# MI0283QT_v12b.net
KiCad netlist of a schematic drawn in EAGLE
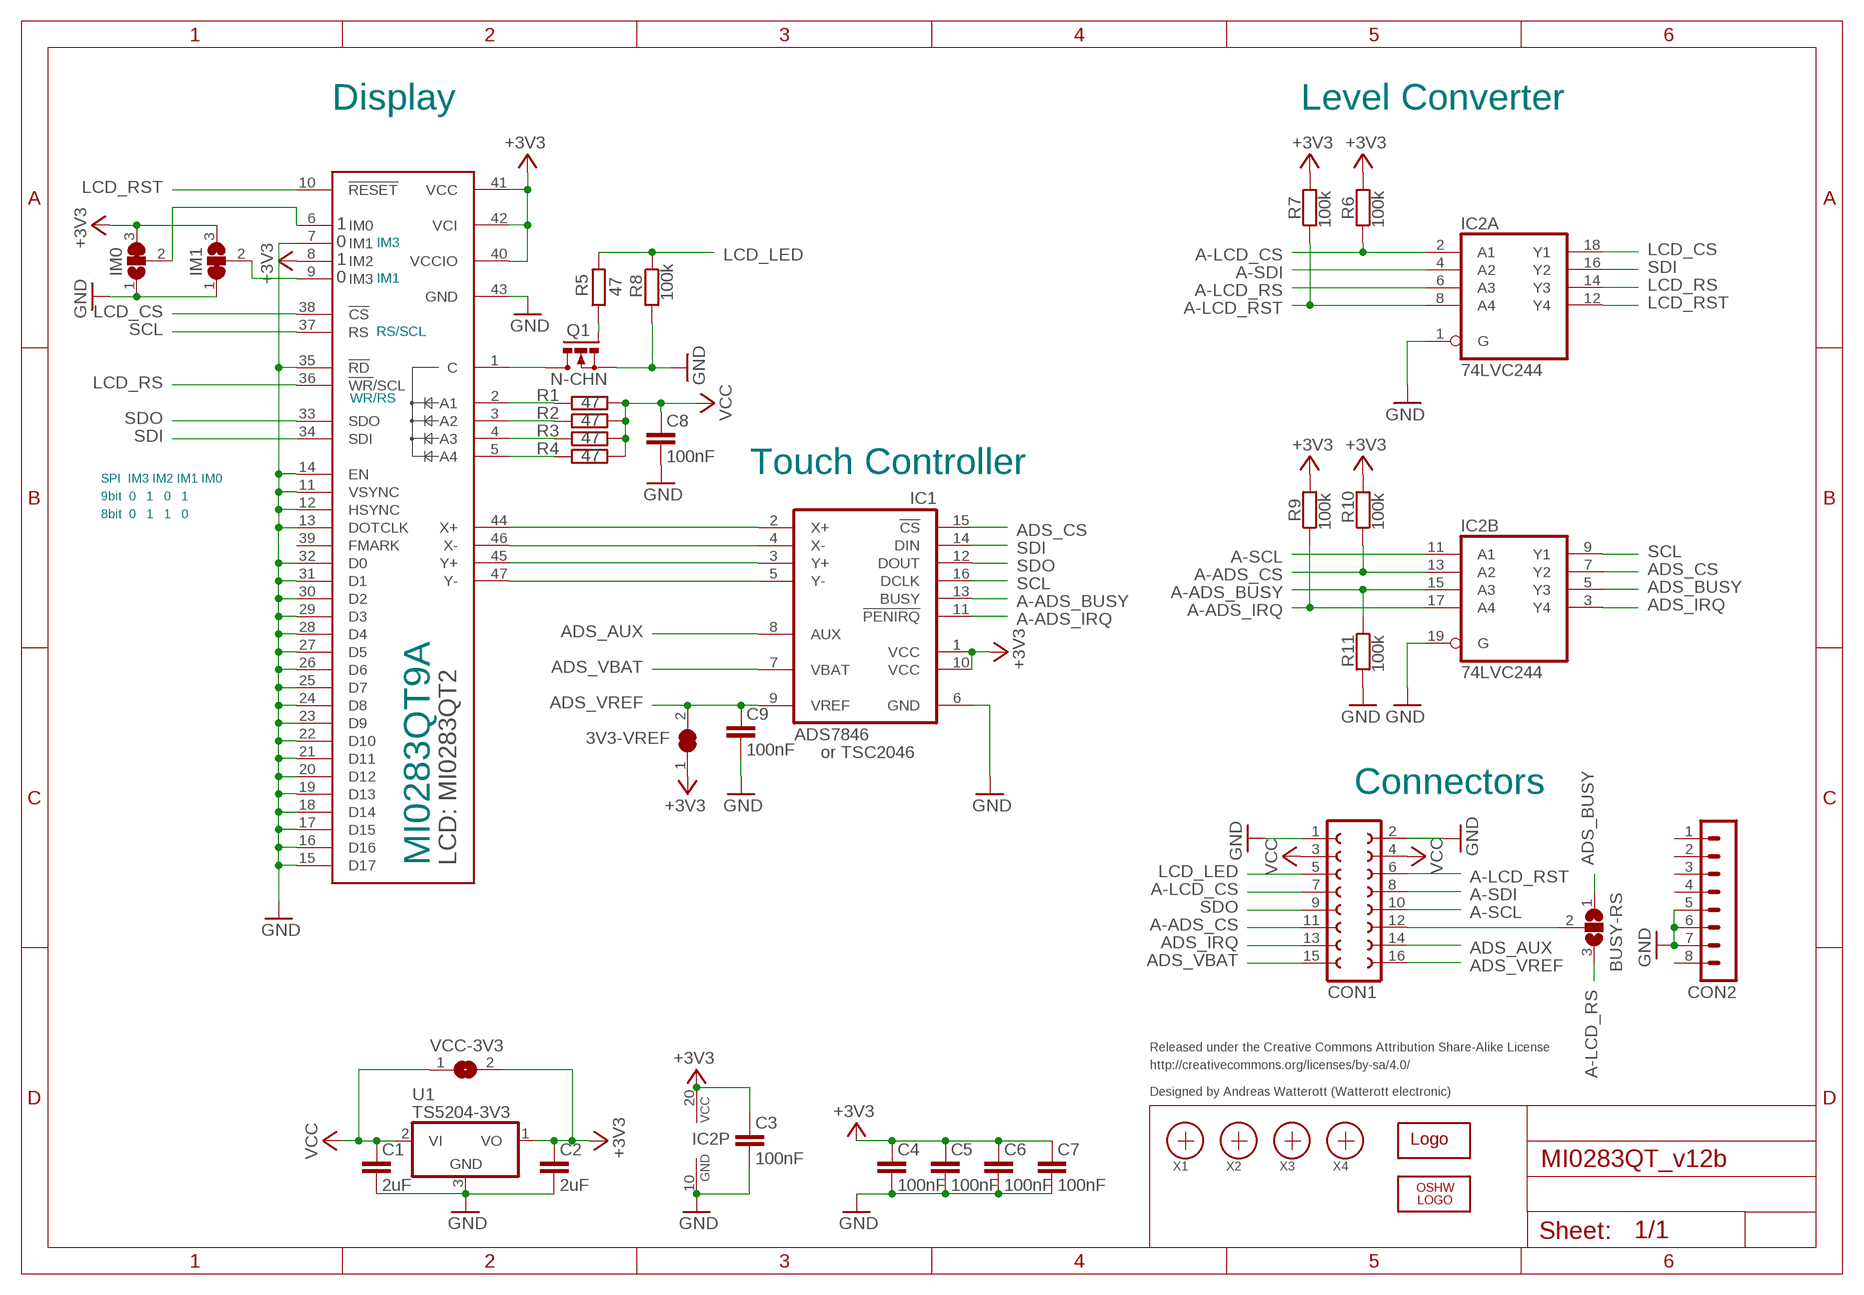
[diagram p0: schematic, sheet 1]

(export (version "E")
  (design (tool "Eeschema 10.0.6"))
  (components
    (comp (ref "3V3-VREF")
      (value "SJ")
      (footprint "eagle-import:SJ")
      (libsource (lib "eagle-import") (part "SJ"))
    )
    (comp (ref "BUSY-RS")
      (value "SJ2W")
      (footprint "eagle-import:SJ_2")
      (libsource (lib "eagle-import") (part "SJ2W"))
    )
    (comp (ref "C1")
      (value "2uF")
      (footprint "eagle-import:C0805")
      (libsource (lib "eagle-import") (part "C-EUC0805"))
    )
    (comp (ref "C2")
      (value "2uF")
      (footprint "eagle-import:C0805")
      (libsource (lib "eagle-import") (part "C-EUC0805"))
    )
    (comp (ref "C3")
      (value "100nF")
      (footprint "eagle-import:C0603")
      (libsource (lib "eagle-import") (part "C-EUC0603"))
    )
    (comp (ref "C4")
      (value "100nF")
      (footprint "eagle-import:C0603")
      (libsource (lib "eagle-import") (part "C-EUC0603"))
    )
    (comp (ref "C5")
      (value "100nF")
      (footprint "eagle-import:C0603")
      (libsource (lib "eagle-import") (part "C-EUC0603"))
    )
    (comp (ref "C6")
      (value "100nF")
      (footprint "eagle-import:C0603")
      (libsource (lib "eagle-import") (part "C-EUC0603"))
    )
    (comp (ref "C7")
      (value "100nF")
      (footprint "eagle-import:C0603")
      (libsource (lib "eagle-import") (part "C-EUC0603"))
    )
    (comp (ref "C8")
      (value "100nF")
      (footprint "eagle-import:C0603")
      (libsource (lib "eagle-import") (part "C-EUC0603"))
    )
    (comp (ref "C9")
      (value "100nF")
      (footprint "eagle-import:C0603")
      (libsource (lib "eagle-import") (part "C-EUC0603"))
    )
    (comp (ref "CON1")
      (value "FE08-2")
      (footprint "eagle-import:FE08-2")
      (libsource (lib "eagle-import") (part "FE08-2"))
    )
    (comp (ref "CON2")
      (value "MA08-1")
      (footprint "eagle-import:MA08-1")
      (libsource (lib "eagle-import") (part "MA08-1"))
    )
    (comp (ref "IC1")
      (value "ADS7846")
      (footprint "eagle-import:SSOP16")
      (libsource (lib "eagle-import") (part "ADS7846"))
    )
    (comp (ref "IC2")
      (value "74LVC244")
      (footprint "eagle-import:SO20W")
      (libsource (lib "eagle-import") (part "74244DWHC"))
    )
    (comp (ref "IM0")
      (value "SJ2W")
      (footprint "eagle-import:SJ_2")
      (libsource (lib "eagle-import") (part "SJ2W"))
    )
    (comp (ref "IM1")
      (value "SJ2W")
      (footprint "eagle-import:SJ_2")
      (libsource (lib "eagle-import") (part "SJ2W"))
    )
    (comp (ref "LCD")
      (value "MI0283QT")
      (footprint "eagle-import:MI0283QT")
      (libsource (lib "eagle-import") (part "MI0283QT"))
    )
    (comp (ref "LOGO1")
      (value "OSHW_LOGO_6MILX0150-NT")
      (footprint "eagle-import:OSHW_6X150_NOTEXT")
      (libsource (lib "eagle-import") (part "OSHW_LOGO_6MILX0150-NT"))
    )
    (comp (ref "Q1")
      (value "N-CHN")
      (footprint "eagle-import:MICRO3")
      (libsource (lib "eagle-import") (part "IRLML2502"))
    )
    (comp (ref "R1")
      (value "47")
      (footprint "eagle-import:R0603")
      (libsource (lib "eagle-import") (part "R-EU_R0603"))
    )
    (comp (ref "R2")
      (value "47")
      (footprint "eagle-import:R0603")
      (libsource (lib "eagle-import") (part "R-EU_R0603"))
    )
    (comp (ref "R3")
      (value "47")
      (footprint "eagle-import:R0603")
      (libsource (lib "eagle-import") (part "R-EU_R0603"))
    )
    (comp (ref "R4")
      (value "47")
      (footprint "eagle-import:R0603")
      (libsource (lib "eagle-import") (part "R-EU_R0603"))
    )
    (comp (ref "R5")
      (value "47")
      (footprint "eagle-import:R0603")
      (libsource (lib "eagle-import") (part "R-EU_R0603"))
    )
    (comp (ref "R6")
      (value "100k")
      (footprint "eagle-import:R0603")
      (libsource (lib "eagle-import") (part "R-EU_R0603"))
    )
    (comp (ref "R7")
      (value "100k")
      (footprint "eagle-import:R0603")
      (libsource (lib "eagle-import") (part "R-EU_R0603"))
    )
    (comp (ref "R8")
      (value "100k")
      (footprint "eagle-import:R0603")
      (libsource (lib "eagle-import") (part "R-EU_R0603"))
    )
    (comp (ref "R9")
      (value "100k")
      (footprint "eagle-import:R0603")
      (libsource (lib "eagle-import") (part "R-EU_R0603"))
    )
    (comp (ref "R10")
      (value "100k")
      (footprint "eagle-import:R0603")
      (libsource (lib "eagle-import") (part "R-EU_R0603"))
    )
    (comp (ref "R11")
      (value "100k")
      (footprint "eagle-import:R0603")
      (libsource (lib "eagle-import") (part "R-EU_R0603"))
    )
    (comp (ref "U$1")
      (value "WE-LOGO")
      (footprint "eagle-import:WE-LOGO")
      (libsource (lib "eagle-import") (part "WE-LOGO"))
    )
    (comp (ref "U1")
      (value "TS5204-3V3")
      (footprint "eagle-import:SOT23")
      (libsource (lib "eagle-import") (part "TS5204"))
    )
    (comp (ref "VCC-3V3")
      (value "SJ")
      (footprint "eagle-import:SJ")
      (libsource (lib "eagle-import") (part "SJ"))
    )
    (comp (ref "X1")
      (value "PASSER")
      (footprint "eagle-import:PASSER")
      (libsource (lib "eagle-import") (part "PASSER"))
    )
    (comp (ref "X2")
      (value "PASSER")
      (footprint "eagle-import:PASSER")
      (libsource (lib "eagle-import") (part "PASSER"))
    )
    (comp (ref "X3")
      (value "PASSER")
      (footprint "eagle-import:PASSER")
      (libsource (lib "eagle-import") (part "PASSER"))
    )
    (comp (ref "X4")
      (value "PASSER")
      (footprint "eagle-import:PASSER")
      (libsource (lib "eagle-import") (part "PASSER"))
    )
  )
  (nets
    (net (code "1") (name "+3V3") (class "Default")
      (node (ref "3V3-VREF") (pin "1") (pinfunction "1_1") (pintype "passive"))
      (node (ref "C2") (pin "1") (pinfunction "1_1") (pintype "passive"))
      (node (ref "C3") (pin "1") (pinfunction "1_1") (pintype "passive"))
      (node (ref "C4") (pin "1") (pinfunction "1_1") (pintype "passive"))
      (node (ref "C5") (pin "1") (pinfunction "1_1") (pintype "passive"))
      (node (ref "C6") (pin "1") (pinfunction "1_1") (pintype "passive"))
      (node (ref "C7") (pin "1") (pinfunction "1_1") (pintype "passive"))
      (node (ref "IC1") (pin "1") (pinfunction "VCC_1") (pintype "power_in"))
      (node (ref "IC1") (pin "10") (pinfunction "VCC_10") (pintype "power_in"))
      (node (ref "IC2") (pin "20") (pinfunction "VCC_20") (pintype "power_in"))
      (node (ref "IM0") (pin "3") (pinfunction "3_3") (pintype "passive"))
      (node (ref "IM1") (pin "3") (pinfunction "3_3") (pintype "passive"))
      (node (ref "LCD") (pin "40") (pinfunction "VCCIO_40") (pintype "power_in"))
      (node (ref "LCD") (pin "41") (pinfunction "VCC_41") (pintype "power_in"))
      (node (ref "LCD") (pin "42") (pinfunction "VCI_42") (pintype "power_in"))
      (node (ref "LCD") (pin "8") (pinfunction "IM2_8") (pintype "input"))
      (node (ref "R10") (pin "2") (pinfunction "2_2") (pintype "passive"))
      (node (ref "R6") (pin "2") (pinfunction "2_2") (pintype "passive"))
      (node (ref "R7") (pin "2") (pinfunction "2_2") (pintype "passive"))
      (node (ref "R9") (pin "2") (pinfunction "2_2") (pintype "passive"))
      (node (ref "U1") (pin "1") (pinfunction "VO_1") (pintype "passive"))
      (node (ref "VCC-3V3") (pin "2") (pinfunction "2_2") (pintype "passive"))
    )
    (net (code "2") (name "/A-ADS_BUSY") (class "Default")
      (node (ref "IC1") (pin "13") (pinfunction "BUSY_13") (pintype "output"))
      (node (ref "IC2") (pin "15") (pinfunction "A3_15") (pintype "input"))
      (node (ref "R11") (pin "1") (pinfunction "1_1") (pintype "passive"))
    )
    (net (code "3") (name "/A-ADS_CS") (class "Default")
      (node (ref "CON1") (pin "11") (pinfunction "11_11") (pintype "passive"))
      (node (ref "IC2") (pin "13") (pinfunction "A2_13") (pintype "input"))
      (node (ref "R10") (pin "1") (pinfunction "1_1") (pintype "passive"))
    )
    (net (code "4") (name "/A-ADS_IRQ") (class "Default")
      (node (ref "IC1") (pin "11") (pinfunction "~{PENIRQ}_11") (pintype "output"))
      (node (ref "IC2") (pin "17") (pinfunction "A4_17") (pintype "input"))
      (node (ref "R9") (pin "1") (pinfunction "1_1") (pintype "passive"))
    )
    (net (code "5") (name "/A-LCD_CS") (class "Default")
      (node (ref "CON1") (pin "7") (pinfunction "7_7") (pintype "passive"))
      (node (ref "IC2") (pin "2") (pinfunction "A1_2") (pintype "input"))
      (node (ref "R6") (pin "1") (pinfunction "1_1") (pintype "passive"))
    )
    (net (code "6") (name "/A-LCD_RS") (class "Default")
      (node (ref "BUSY-RS") (pin "3") (pinfunction "3_3") (pintype "passive"))
      (node (ref "IC2") (pin "6") (pinfunction "A3_6") (pintype "input"))
    )
    (net (code "7") (name "/A-LCD_RST") (class "Default")
      (node (ref "CON1") (pin "6") (pinfunction "6_6") (pintype "passive"))
      (node (ref "IC2") (pin "8") (pinfunction "A4_8") (pintype "input"))
      (node (ref "R7") (pin "1") (pinfunction "1_1") (pintype "passive"))
    )
    (net (code "8") (name "/A-SCL") (class "Default")
      (node (ref "CON1") (pin "10") (pinfunction "10_10") (pintype "passive"))
      (node (ref "IC2") (pin "11") (pinfunction "A1_11") (pintype "input"))
    )
    (net (code "9") (name "/A-SDI") (class "Default")
      (node (ref "CON1") (pin "8") (pinfunction "8_8") (pintype "passive"))
      (node (ref "IC2") (pin "4") (pinfunction "A2_4") (pintype "input"))
    )
    (net (code "10") (name "/ADS_AUX") (class "Default")
      (node (ref "CON1") (pin "14") (pinfunction "14_14") (pintype "passive"))
      (node (ref "IC1") (pin "8") (pinfunction "AUX_8") (pintype "input"))
    )
    (net (code "11") (name "/ADS_BUSY") (class "Default")
      (node (ref "BUSY-RS") (pin "1") (pinfunction "1_1") (pintype "passive"))
      (node (ref "IC2") (pin "5") (pinfunction "Y3_5") (pintype "tri_state"))
    )
    (net (code "12") (name "/ADS_CS") (class "Default")
      (node (ref "IC1") (pin "15") (pinfunction "~{CS}_15") (pintype "input"))
      (node (ref "IC2") (pin "7") (pinfunction "Y2_7") (pintype "tri_state"))
    )
    (net (code "13") (name "/ADS_IRQ") (class "Default")
      (node (ref "CON1") (pin "13") (pinfunction "13_13") (pintype "passive"))
      (node (ref "IC2") (pin "3") (pinfunction "Y4_3") (pintype "tri_state"))
    )
    (net (code "14") (name "/ADS_VBAT") (class "Default")
      (node (ref "CON1") (pin "15") (pinfunction "15_15") (pintype "passive"))
      (node (ref "IC1") (pin "7") (pinfunction "VBAT_7") (pintype "input"))
    )
    (net (code "15") (name "/ADS_VREF") (class "Default")
      (node (ref "3V3-VREF") (pin "2") (pinfunction "2_2") (pintype "passive"))
      (node (ref "C9") (pin "1") (pinfunction "1_1") (pintype "passive"))
      (node (ref "CON1") (pin "16") (pinfunction "16_16") (pintype "passive"))
      (node (ref "IC1") (pin "9") (pinfunction "VREF_9") (pintype "bidirectional"))
    )
    (net (code "16") (name "/LCD_CS") (class "Default")
      (node (ref "IC2") (pin "18") (pinfunction "Y1_18") (pintype "tri_state"))
      (node (ref "LCD") (pin "38") (pinfunction "~{CS}_38") (pintype "input"))
    )
    (net (code "17") (name "/LCD_LED") (class "Default")
      (node (ref "CON1") (pin "5") (pinfunction "5_5") (pintype "passive"))
      (node (ref "R5") (pin "2") (pinfunction "2_2") (pintype "passive"))
      (node (ref "R8") (pin "1") (pinfunction "1_1") (pintype "passive"))
    )
    (net (code "18") (name "/LCD_RS") (class "Default")
      (node (ref "IC2") (pin "14") (pinfunction "Y3_14") (pintype "tri_state"))
      (node (ref "LCD") (pin "36") (pinfunction "~{WR}/SCL_36") (pintype "input"))
    )
    (net (code "19") (name "/LCD_RST") (class "Default")
      (node (ref "IC2") (pin "12") (pinfunction "Y4_12") (pintype "tri_state"))
      (node (ref "LCD") (pin "10") (pinfunction "~{RESET}_10") (pintype "input"))
    )
    (net (code "20") (name "/SCL") (class "Default")
      (node (ref "IC1") (pin "16") (pinfunction "DCLK_16") (pintype "output"))
      (node (ref "IC2") (pin "9") (pinfunction "Y1_9") (pintype "tri_state"))
      (node (ref "LCD") (pin "37") (pinfunction "RS_37") (pintype "input"))
    )
    (net (code "21") (name "/SDI") (class "Default")
      (node (ref "IC1") (pin "14") (pinfunction "DIN_14") (pintype "input"))
      (node (ref "IC2") (pin "16") (pinfunction "Y2_16") (pintype "tri_state"))
      (node (ref "LCD") (pin "34") (pinfunction "SDI_34") (pintype "input"))
    )
    (net (code "22") (name "/SDO") (class "Default")
      (node (ref "CON1") (pin "9") (pinfunction "9_9") (pintype "passive"))
      (node (ref "IC1") (pin "12") (pinfunction "DOUT_12") (pintype "input"))
      (node (ref "LCD") (pin "33") (pinfunction "SDO_33") (pintype "output"))
    )
    (net (code "23") (name "GND") (class "Default")
      (node (ref "C1") (pin "2") (pinfunction "2_2") (pintype "passive"))
      (node (ref "C2") (pin "2") (pinfunction "2_2") (pintype "passive"))
      (node (ref "C3") (pin "2") (pinfunction "2_2") (pintype "passive"))
      (node (ref "C4") (pin "2") (pinfunction "2_2") (pintype "passive"))
      (node (ref "C5") (pin "2") (pinfunction "2_2") (pintype "passive"))
      (node (ref "C6") (pin "2") (pinfunction "2_2") (pintype "passive"))
      (node (ref "C7") (pin "2") (pinfunction "2_2") (pintype "passive"))
      (node (ref "C8") (pin "2") (pinfunction "2_2") (pintype "passive"))
      (node (ref "C9") (pin "2") (pinfunction "2_2") (pintype "passive"))
      (node (ref "CON1") (pin "1") (pinfunction "1_1") (pintype "passive"))
      (node (ref "CON1") (pin "2") (pinfunction "2_2") (pintype "passive"))
      (node (ref "CON2") (pin "5") (pinfunction "5_5") (pintype "passive"))
      (node (ref "CON2") (pin "6") (pinfunction "6_6") (pintype "passive"))
      (node (ref "CON2") (pin "7") (pinfunction "7_7") (pintype "passive"))
      (node (ref "IC1") (pin "6") (pinfunction "GND_6") (pintype "power_in"))
      (node (ref "IC2") (pin "1") (pinfunction "G_1") (pintype "input"))
      (node (ref "IC2") (pin "10") (pinfunction "GND_10") (pintype "power_in"))
      (node (ref "IC2") (pin "19") (pinfunction "G_19") (pintype "input"))
      (node (ref "IM0") (pin "1") (pinfunction "1_1") (pintype "passive"))
      (node (ref "IM1") (pin "1") (pinfunction "1_1") (pintype "passive"))
      (node (ref "LCD") (pin "11") (pinfunction "VSYNC_11") (pintype "input"))
      (node (ref "LCD") (pin "12") (pinfunction "HSYNC_12") (pintype "input"))
      (node (ref "LCD") (pin "13") (pinfunction "DOTCLK_13") (pintype "input"))
      (node (ref "LCD") (pin "14") (pinfunction "EN_14") (pintype "input"))
      (node (ref "LCD") (pin "15") (pinfunction "D17_15") (pintype "input"))
      (node (ref "LCD") (pin "16") (pinfunction "D16_16") (pintype "input"))
      (node (ref "LCD") (pin "17") (pinfunction "D15_17") (pintype "input"))
      (node (ref "LCD") (pin "18") (pinfunction "D14_18") (pintype "input"))
      (node (ref "LCD") (pin "19") (pinfunction "D13_19") (pintype "input"))
      (node (ref "LCD") (pin "20") (pinfunction "D12_20") (pintype "input"))
      (node (ref "LCD") (pin "21") (pinfunction "D11_21") (pintype "input"))
      (node (ref "LCD") (pin "22") (pinfunction "D10_22") (pintype "input"))
      (node (ref "LCD") (pin "23") (pinfunction "D9_23") (pintype "input"))
      (node (ref "LCD") (pin "24") (pinfunction "D8_24") (pintype "input"))
      (node (ref "LCD") (pin "25") (pinfunction "D7_25") (pintype "input"))
      (node (ref "LCD") (pin "26") (pinfunction "D6_26") (pintype "input"))
      (node (ref "LCD") (pin "27") (pinfunction "D5_27") (pintype "input"))
      (node (ref "LCD") (pin "28") (pinfunction "D4_28") (pintype "input"))
      (node (ref "LCD") (pin "29") (pinfunction "D3_29") (pintype "input"))
      (node (ref "LCD") (pin "30") (pinfunction "D2_30") (pintype "input"))
      (node (ref "LCD") (pin "31") (pinfunction "D1_31") (pintype "input"))
      (node (ref "LCD") (pin "32") (pinfunction "D0_32") (pintype "input"))
      (node (ref "LCD") (pin "35") (pinfunction "~{RD}_35") (pintype "input"))
      (node (ref "LCD") (pin "43") (pinfunction "GND_43") (pintype "power_in"))
      (node (ref "LCD") (pin "7") (pinfunction "IM1_7") (pintype "input"))
      (node (ref "Q1") (pin "2") (pinfunction "S_2") (pintype "passive"))
      (node (ref "R11") (pin "2") (pinfunction "2_2") (pintype "passive"))
      (node (ref "R8") (pin "2") (pinfunction "2_2") (pintype "passive"))
      (node (ref "U1") (pin "3") (pinfunction "GND_3") (pintype "passive"))
    )
    (net (code "24") (name "Net-(BUSY-RS-Pad2)") (class "Default")
      (node (ref "BUSY-RS") (pin "2") (pinfunction "2_2") (pintype "passive"))
      (node (ref "CON1") (pin "12") (pinfunction "12_12") (pintype "passive"))
    )
    (net (code "25") (name "Net-(IC1-X+)") (class "Default")
      (node (ref "IC1") (pin "2") (pinfunction "X+_2") (pintype "input"))
      (node (ref "LCD") (pin "44") (pinfunction "X+_44") (pintype "passive"))
    )
    (net (code "26") (name "Net-(IC1-X-)") (class "Default")
      (node (ref "IC1") (pin "4") (pinfunction "X-_4") (pintype "input"))
      (node (ref "LCD") (pin "46") (pinfunction "X-_46") (pintype "passive"))
    )
    (net (code "27") (name "Net-(IC1-Y+)") (class "Default")
      (node (ref "IC1") (pin "3") (pinfunction "Y+_3") (pintype "input"))
      (node (ref "LCD") (pin "45") (pinfunction "Y+_45") (pintype "passive"))
    )
    (net (code "28") (name "Net-(IC1-Y-)") (class "Default")
      (node (ref "IC1") (pin "5") (pinfunction "Y-_5") (pintype "input"))
      (node (ref "LCD") (pin "47") (pinfunction "Y-_47") (pintype "passive"))
    )
    (net (code "29") (name "Net-(LCD-A1)") (class "Default")
      (node (ref "LCD") (pin "2") (pinfunction "A1_2") (pintype "power_in"))
      (node (ref "R1") (pin "1") (pinfunction "1_1") (pintype "passive"))
    )
    (net (code "30") (name "Net-(LCD-A2)") (class "Default")
      (node (ref "LCD") (pin "3") (pinfunction "A2_3") (pintype "power_in"))
      (node (ref "R2") (pin "1") (pinfunction "1_1") (pintype "passive"))
    )
    (net (code "31") (name "Net-(LCD-A3)") (class "Default")
      (node (ref "LCD") (pin "4") (pinfunction "A3_4") (pintype "power_in"))
      (node (ref "R3") (pin "1") (pinfunction "1_1") (pintype "passive"))
    )
    (net (code "32") (name "Net-(LCD-A4)") (class "Default")
      (node (ref "LCD") (pin "5") (pinfunction "A4_5") (pintype "power_in"))
      (node (ref "R4") (pin "1") (pinfunction "1_1") (pintype "passive"))
    )
    (net (code "33") (name "Net-(LCD-C)") (class "Default")
      (node (ref "LCD") (pin "1") (pinfunction "C_1") (pintype "power_in"))
      (node (ref "Q1") (pin "3") (pinfunction "D_3") (pintype "passive"))
    )
    (net (code "34") (name "Net-(LCD-IM0)") (class "Default")
      (node (ref "IM0") (pin "2") (pinfunction "2_2") (pintype "passive"))
      (node (ref "LCD") (pin "6") (pinfunction "IM0_6") (pintype "input"))
    )
    (net (code "35") (name "Net-(LCD-IM3)") (class "Default")
      (node (ref "IM1") (pin "2") (pinfunction "2_2") (pintype "passive"))
      (node (ref "LCD") (pin "9") (pinfunction "IM3_9") (pintype "input"))
    )
    (net (code "36") (name "Net-(Q1-G)") (class "Default")
      (node (ref "Q1") (pin "1") (pinfunction "G_1") (pintype "passive"))
      (node (ref "R5") (pin "1") (pinfunction "1_1") (pintype "passive"))
    )
    (net (code "37") (name "VCC") (class "Default")
      (node (ref "C1") (pin "1") (pinfunction "1_1") (pintype "passive"))
      (node (ref "C8") (pin "1") (pinfunction "1_1") (pintype "passive"))
      (node (ref "CON1") (pin "3") (pinfunction "3_3") (pintype "passive"))
      (node (ref "CON1") (pin "4") (pinfunction "4_4") (pintype "passive"))
      (node (ref "R1") (pin "2") (pinfunction "2_2") (pintype "passive"))
      (node (ref "R2") (pin "2") (pinfunction "2_2") (pintype "passive"))
      (node (ref "R3") (pin "2") (pinfunction "2_2") (pintype "passive"))
      (node (ref "R4") (pin "2") (pinfunction "2_2") (pintype "passive"))
      (node (ref "U1") (pin "2") (pinfunction "VI_2") (pintype "input"))
      (node (ref "VCC-3V3") (pin "1") (pinfunction "1_1") (pintype "passive"))
    )
    (net (code "38") (name "unconnected-(CON2-Pad1)") (class "Default")
      (node (ref "CON2") (pin "1") (pinfunction "1_1") (pintype "passive"))
    )
    (net (code "39") (name "unconnected-(CON2-Pad2)") (class "Default")
      (node (ref "CON2") (pin "2") (pinfunction "2_2") (pintype "passive"))
    )
    (net (code "40") (name "unconnected-(CON2-Pad3)") (class "Default")
      (node (ref "CON2") (pin "3") (pinfunction "3_3") (pintype "passive"))
    )
    (net (code "41") (name "unconnected-(CON2-Pad4)") (class "Default")
      (node (ref "CON2") (pin "4") (pinfunction "4_4") (pintype "passive"))
    )
    (net (code "42") (name "unconnected-(CON2-Pad8)") (class "Default")
      (node (ref "CON2") (pin "8") (pinfunction "8_8") (pintype "passive"))
    )
    (net (code "43") (name "unconnected-(LCD-FMARK-Pad39)") (class "Default")
      (node (ref "LCD") (pin "39") (pinfunction "FMARK_39") (pintype "output"))
    )
  )
)
